# Interface.net
KiCad netlist of a schematic drawn in Altium Designer
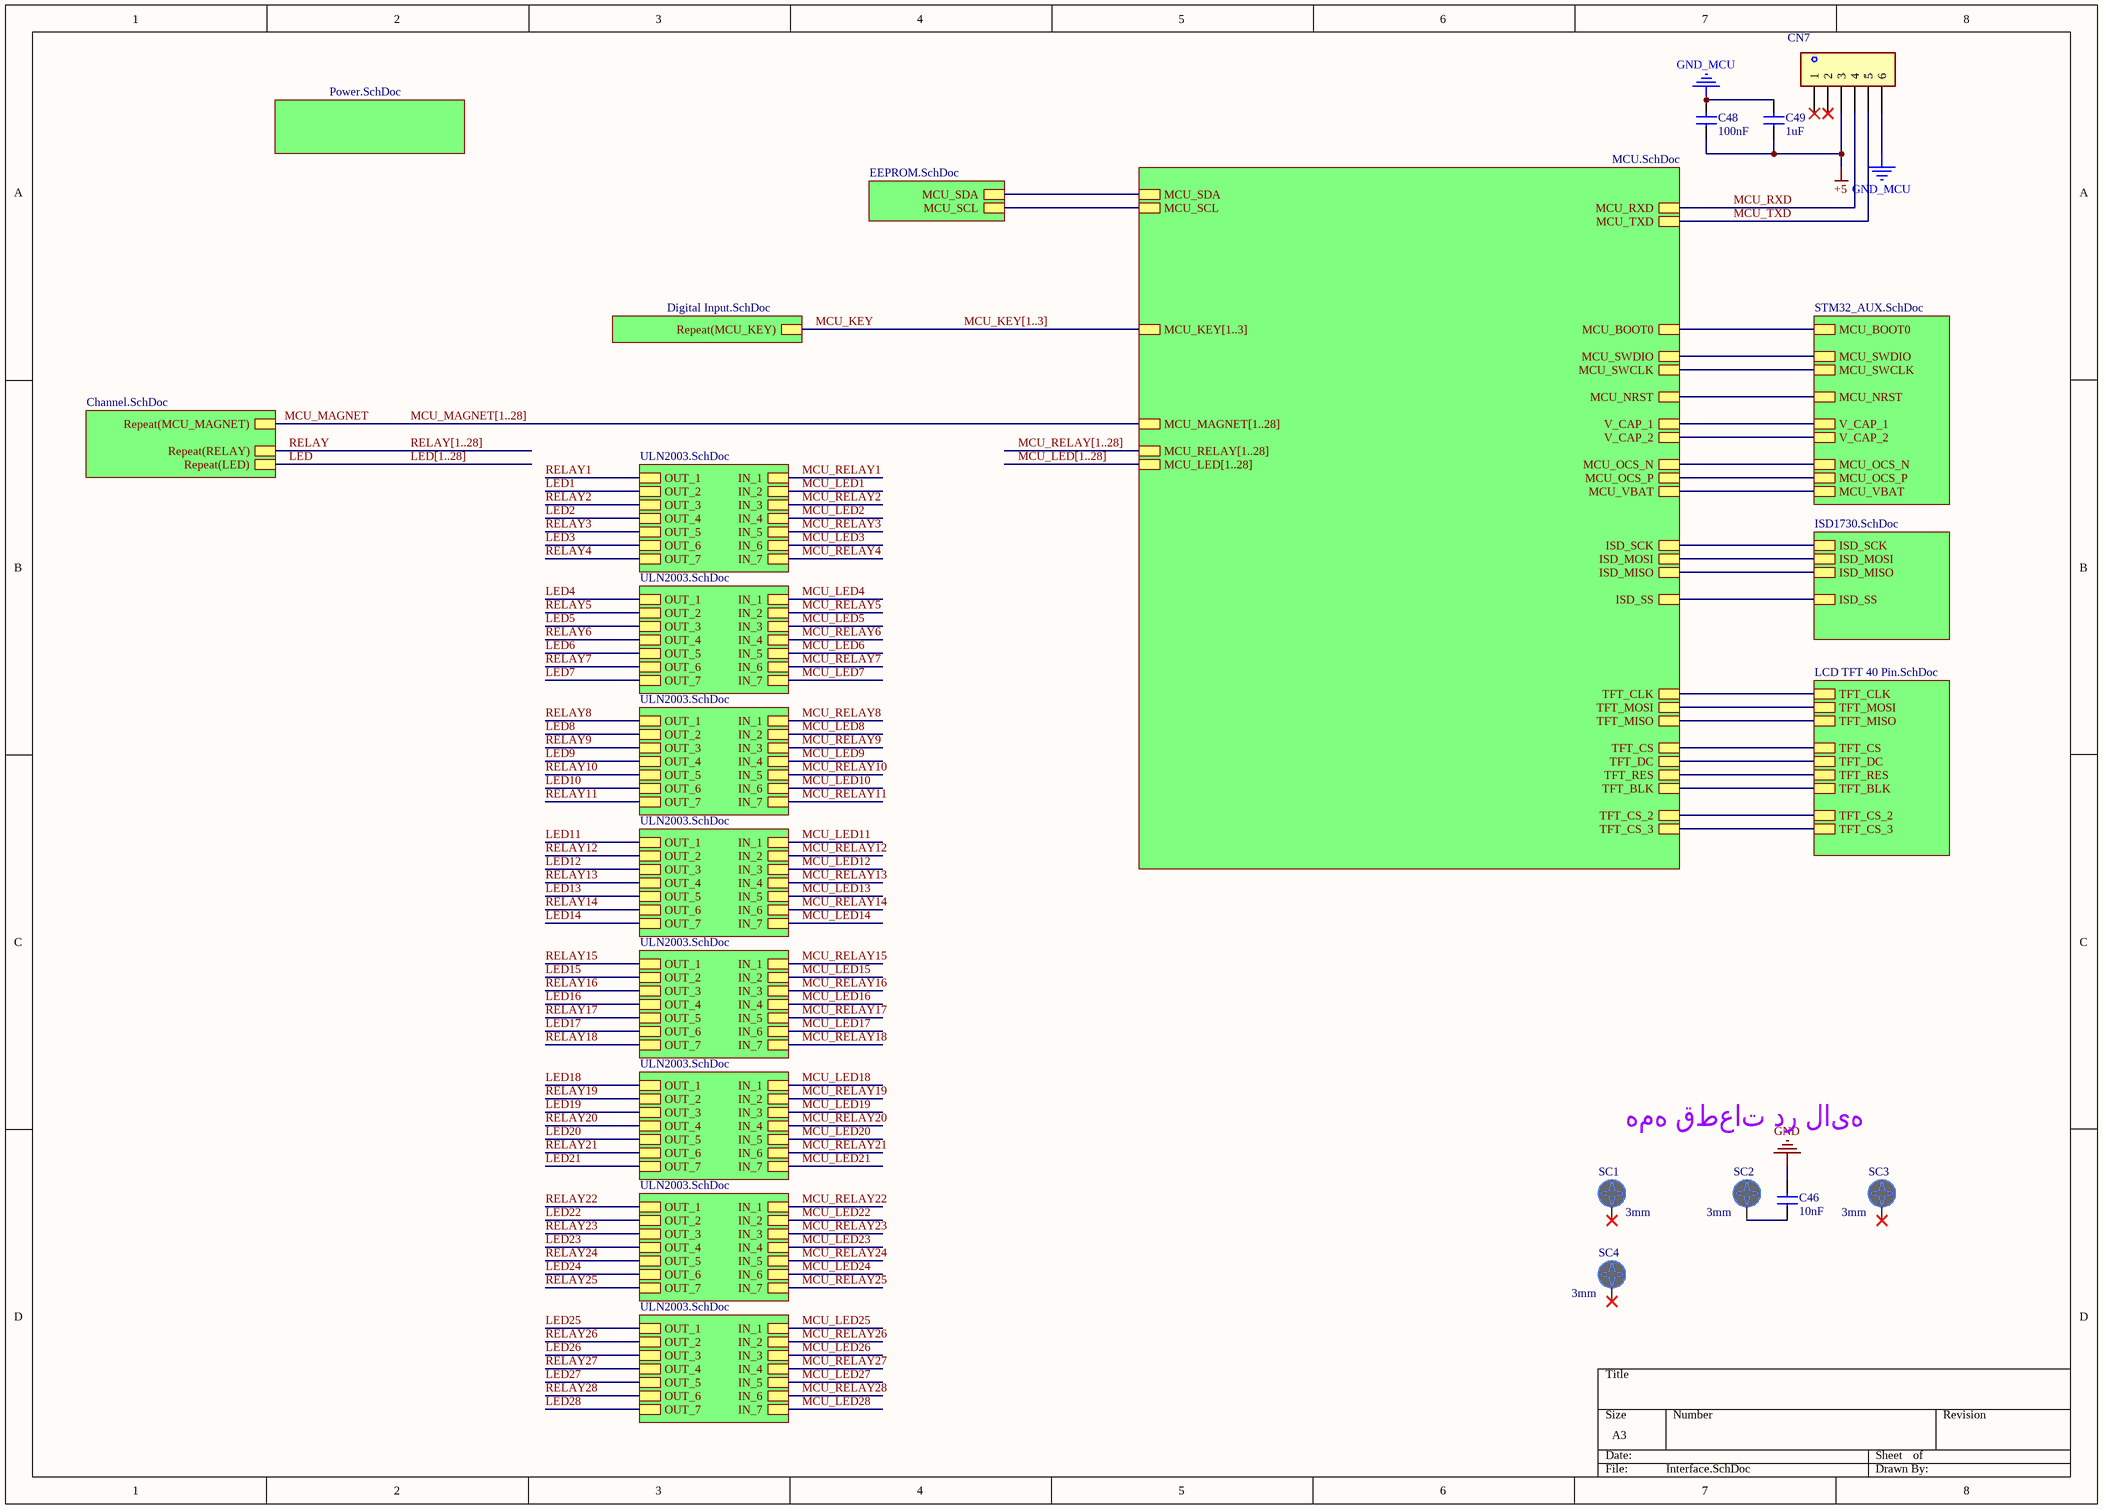
[diagram p0: Interface.SchDoc]

(export (version "E")
  (design (tool "Eeschema 10.0.6"))
  (components
    (comp (ref "C46")
      (value "10nF")
      (footprint "CAP-CER-13x5-Ls10")
      (description "CAPACITOR")
      (fields
        (field (name "VOLTAGE") "1KV")
        (field (name "TOLERANCE") "X7R")
        (field (name "PUBLISHER") "Mahdi Bagherzadeh")
      )
      (libsource (lib "Mahdi-Bagherzadeh") (part "CAP-CER"))
    )
    (comp (ref "C48")
      (value "100nF")
      (footprint "C-0805")
      (description "CAPACITOR")
      (fields
        (field (name "VOLTAGE") "50V")
        (field (name "TOLERANCE") "X7R")
        (field (name "PUBLISHER") "Mahdi Bagherzadeh")
      )
      (libsource (lib "Mahdi-Bagherzadeh") (part "CAP-CER"))
    )
    (comp (ref "C49")
      (value "1uF")
      (footprint "C-0805")
      (description "CAPACITOR")
      (fields
        (field (name "VOLTAGE") "50V")
        (field (name "TOLERANCE") "X7R")
        (field (name "PUBLISHER") "Mahdi Bagherzadeh")
      )
      (libsource (lib "Mahdi-Bagherzadeh") (part "CAP-CER"))
    )
    (comp (ref "CN7")
      (value "Connector XH/VH/TE-Straight/Right-THD/SMD-?mm")
      (footprint "XH-6")
      (description "CONNECTOR")
      (fields (field (name "PUBLISHER") "Mahdi Bagherzadeh"))
      (libsource (lib "Mahdi-Bagherzadeh") (part "CN-6pin"))
    )
    (comp (ref "SC1")
      (value "Screw 3mm")
      (footprint "Screw_M3")
      (description "SCREW")
      (fields (field (name "SIZE") "3mm") (field (name "PUBLISHER") "Mahdi Bagherzadeh"))
      (libsource (lib "Mahdi-Bagherzadeh") (part "SCREW"))
    )
    (comp (ref "SC2")
      (value "Screw 3mm")
      (footprint "Screw_M3")
      (description "SCREW")
      (fields (field (name "SIZE") "3mm") (field (name "PUBLISHER") "Mahdi Bagherzadeh"))
      (libsource (lib "Mahdi-Bagherzadeh") (part "SCREW"))
    )
    (comp (ref "SC3")
      (value "Screw 3mm")
      (footprint "Screw_M3")
      (description "SCREW")
      (fields (field (name "SIZE") "3mm") (field (name "PUBLISHER") "Mahdi Bagherzadeh"))
      (libsource (lib "Mahdi-Bagherzadeh") (part "SCREW"))
    )
    (comp (ref "SC4")
      (value "Screw 3mm")
      (footprint "Screw_M3")
      (description "SCREW")
      (fields (field (name "SIZE") "3mm") (field (name "PUBLISHER") "Mahdi Bagherzadeh"))
      (libsource (lib "Mahdi-Bagherzadeh") (part "SCREW"))
    )
  )
  (nets
    (net (code "29") (name "+5") (class "Default")
      (node (ref "C48") (pin "1") (pinfunction "1_1") (pintype "passive"))
      (node (ref "C49") (pin "1") (pinfunction "1_1") (pintype "passive"))
      (node (ref "CN7") (pin "3") (pinfunction "3_3") (pintype "passive"))
    )
    (net (code "129") (name "/MCU_RXD") (class "Default")
      (node (ref "CN7") (pin "4") (pinfunction "4_4") (pintype "passive"))
    )
    (net (code "134") (name "/MCU_TXD") (class "Default")
      (node (ref "CN7") (pin "5") (pinfunction "5_5") (pintype "passive"))
    )
    (net (code "177") (name "GND") (class "Default")
      (node (ref "C46") (pin "2") (pinfunction "2_2") (pintype "passive"))
    )
    (net (code "178") (name "GND_MCU") (class "Default")
      (node (ref "C48") (pin "2") (pinfunction "2_2") (pintype "passive"))
      (node (ref "C49") (pin "2") (pinfunction "2_2") (pintype "passive"))
      (node (ref "CN7") (pin "6") (pinfunction "6_6") (pintype "passive"))
    )
    (net (code "179") (name "Net-(C46-Pad1)") (class "Default")
      (node (ref "C46") (pin "1") (pinfunction "1_1") (pintype "passive"))
      (node (ref "SC2") (pin "1") (pinfunction "1_1") (pintype "passive"))
    )
    (net (code "180") (name "unconnected-(CN7-Pad1)") (class "Default")
      (node (ref "CN7") (pin "1") (pinfunction "1_1") (pintype "passive+no_connect"))
    )
    (net (code "181") (name "unconnected-(CN7-Pad2)") (class "Default")
      (node (ref "CN7") (pin "2") (pinfunction "2_2") (pintype "passive+no_connect"))
    )
    (net (code "182") (name "unconnected-(SC1-Pad1)") (class "Default")
      (node (ref "SC1") (pin "1") (pinfunction "1_1") (pintype "passive+no_connect"))
    )
    (net (code "183") (name "unconnected-(SC3-Pad1)") (class "Default")
      (node (ref "SC3") (pin "1") (pinfunction "1_1") (pintype "passive+no_connect"))
    )
    (net (code "184") (name "unconnected-(SC4-Pad1)") (class "Default")
      (node (ref "SC4") (pin "1") (pinfunction "1_1") (pintype "passive+no_connect"))
    )
  )
)
